# Input_Filter.net
KiCad netlist of a schematic drawn in Altium Designer
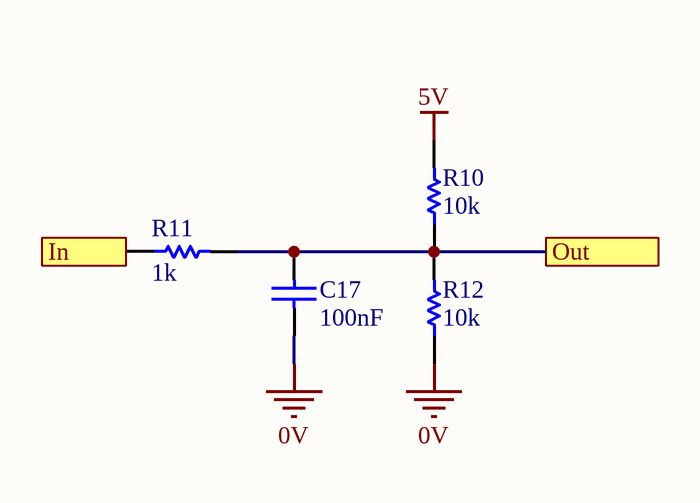
[diagram p0: Input Filter.SchDoc]

(export (version "E")
  (design (tool "Eeschema 10.0.6"))
  (components
    (comp (ref "C17")
      (value "100nF")
      (footprint "0805")
      (fields
        (field (name "PART NUMBER") "GCM21BR71E104KA37L")
        (field (name "TOLERANCE") "10%")
        (field (name "MANUFACTURER") "muRata")
      )
      (libsource (lib "ts_20-standard-library") (part "Capacitor"))
    )
    (comp (ref "R10")
      (value "10k")
      (footprint "0805")
      (fields
        (field (name "PART NUMBER") "RC0805FR0710KL")
        (field (name "MANUFACTURER") "YAGEO")
        (field (name "TOLERANCE") "0.01")
      )
      (libsource (lib "ts_20-standard-library") (part "Resistor"))
    )
    (comp (ref "R11")
      (value "1k")
      (footprint "0805")
      (fields
        (field (name "PART NUMBER") "RC0805FR071KL")
        (field (name "MANUFACTURER") "YAGEO")
        (field (name "TOLERANCE") "0.01")
      )
      (libsource (lib "ts_20-standard-library") (part "Resistor"))
    )
    (comp (ref "R12")
      (value "10k")
      (footprint "0805")
      (fields
        (field (name "PART NUMBER") "RC0805FR0710KL")
        (field (name "MANUFACTURER") "YAGEO")
        (field (name "TOLERANCE") "0.01")
      )
      (libsource (lib "ts_20-standard-library") (part "Resistor"))
    )
  )
  (nets
    (net (code "1") (name "/In") (class "Default")
      (node (ref "R11") (pin "1") (pinfunction "1_1") (pintype "passive"))
    )
    (net (code "2") (name "/Out") (class "Default")
      (node (ref "C17") (pin "2") (pinfunction "2_2") (pintype "passive"))
      (node (ref "R10") (pin "1") (pinfunction "1_1") (pintype "passive"))
      (node (ref "R11") (pin "2") (pinfunction "2_2") (pintype "passive"))
      (node (ref "R12") (pin "2") (pinfunction "2_2") (pintype "passive"))
    )
    (net (code "3") (name "0V") (class "Default")
      (node (ref "C17") (pin "1") (pinfunction "1_1") (pintype "passive"))
      (node (ref "R12") (pin "1") (pinfunction "1_1") (pintype "passive"))
    )
    (net (code "4") (name "5V") (class "Default")
      (node (ref "R10") (pin "2") (pinfunction "2_2") (pintype "passive"))
    )
  )
)
